# POW.net
KiCad netlist of a schematic drawn in Altium Designer
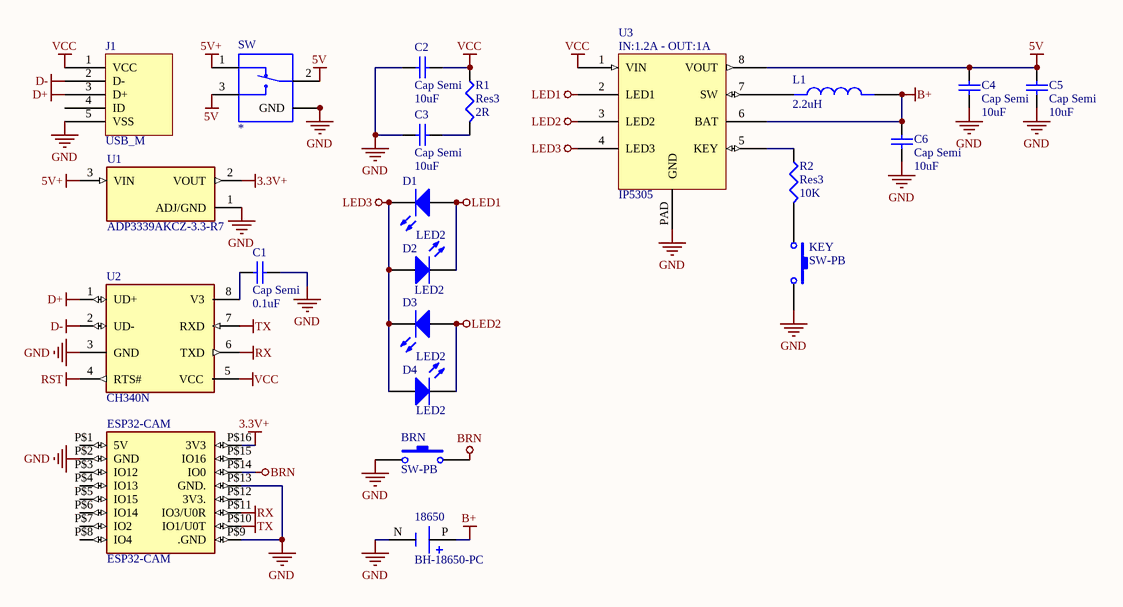
[diagram p0: POW.SchDoc]

(export (version "E")
  (design (tool "Eeschema 10.0.6"))
  (components
    (comp (ref "18650")
      (value "BH-18650-PC")
      (footprint "BAT_BH-18650-PC")
      (description "Battery Holder _Open_ 18650 1 Cell PC Pin")
      (fields (field (name "MF") "MPD _Memory"))
      (libsource (lib "BH-18650-PC") (part "BH-18650-PC"))
    )
    (comp (ref "BRN")
      (value "SW-PB")
      (footprint "SW_PB2_B1")
      (description "峚雄羲壽")
      (fields (field (name "PUBLISHER") "Altium Limited"))
      (libsource (lib "Fszhang") (part "SW-PB"))
    )
    (comp (ref "C1")
      (value "Cap Semi")
      (footprint "C1206")
      (description "Capacitor (Semiconductor SIM Model)")
      (fields (field (name "ALTIUM_VALUE") "0.1uF") (field (name "PUBLISHER") "Altium Limited"))
      (libsource (lib "Miscellaneous Devices") (part "Cap Semi"))
    )
    (comp (ref "C2")
      (value "Cap Semi")
      (footprint "C1210")
      (description "Capacitor (Semiconductor SIM Model)")
      (fields (field (name "ALTIUM_VALUE") "10uF") (field (name "PUBLISHER") "Altium Limited"))
      (libsource (lib "Miscellaneous Devices") (part "Cap Semi"))
    )
    (comp (ref "C3")
      (value "Cap Semi")
      (footprint "C1210")
      (description "Capacitor (Semiconductor SIM Model)")
      (fields (field (name "ALTIUM_VALUE") "10uF") (field (name "PUBLISHER") "Altium Limited"))
      (libsource (lib "Miscellaneous Devices") (part "Cap Semi"))
    )
    (comp (ref "C4")
      (value "Cap Semi")
      (footprint "C1210")
      (description "Capacitor (Semiconductor SIM Model)")
      (fields (field (name "ALTIUM_VALUE") "10uF") (field (name "PUBLISHER") "Altium Limited"))
      (libsource (lib "Miscellaneous Devices") (part "Cap Semi"))
    )
    (comp (ref "C5")
      (value "Cap Semi")
      (footprint "C1210")
      (description "Capacitor (Semiconductor SIM Model)")
      (fields (field (name "ALTIUM_VALUE") "10uF") (field (name "PUBLISHER") "Altium Limited"))
      (libsource (lib "Miscellaneous Devices") (part "Cap Semi"))
    )
    (comp (ref "C6")
      (value "Cap Semi")
      (footprint "C1210")
      (description "Capacitor (Semiconductor SIM Model)")
      (fields (field (name "ALTIUM_VALUE") "10uF") (field (name "PUBLISHER") "Altium Limited"))
      (libsource (lib "Miscellaneous Devices") (part "Cap Semi"))
    )
    (comp (ref "D1")
      (value "LED2")
      (footprint "3.2X1.6X1.1")
      (description "Typical RED, GREEN, YELLOW, AMBER GaAs LED")
      (fields (field (name "PUBLISHER") "Altium Limited"))
      (libsource (lib "Miscellaneous Devices") (part "LED2"))
    )
    (comp (ref "D2")
      (value "LED2")
      (footprint "3.2X1.6X1.1")
      (description "Typical RED, GREEN, YELLOW, AMBER GaAs LED")
      (fields (field (name "PUBLISHER") "Altium Limited"))
      (libsource (lib "Miscellaneous Devices") (part "LED2"))
    )
    (comp (ref "D3")
      (value "LED2")
      (footprint "3.2X1.6X1.1")
      (description "Typical RED, GREEN, YELLOW, AMBER GaAs LED")
      (fields (field (name "PUBLISHER") "Altium Limited"))
      (libsource (lib "Miscellaneous Devices") (part "LED2"))
    )
    (comp (ref "D4")
      (value "LED2")
      (footprint "3.2X1.6X1.1")
      (description "Typical RED, GREEN, YELLOW, AMBER GaAs LED")
      (fields (field (name "PUBLISHER") "Altium Limited"))
      (libsource (lib "Miscellaneous Devices") (part "LED2"))
    )
    (comp (ref "ESP32-CAM")
      (value "ESP32-CAM")
      (footprint "ESP32-CAM")
      (description "The smallest 802.11b/g/n Wi-Fi BT SoC Module")
      (fields (field (name "MF") "AI-Thinker"))
      (libsource (lib "ESP32-CAM") (part "ESP32-CAM"))
    )
    (comp (ref "J1")
      (value "USB_M")
      (footprint "USB_MICRO")
      (description "MicroUSB諉諳")
      (libsource (lib "Fszhang") (part "USB_M"))
    )
    (comp (ref "KEY")
      (value "SW-PB")
      (footprint "SW_PB2_B1")
      (description "峚雄羲壽")
      (fields (field (name "PUBLISHER") "Altium Limited"))
      (libsource (lib "Fszhang") (part "SW-PB"))
    )
    (comp (ref "L1")
      (value "2.2uH")
      (footprint "IND_1253AY-100M=P3")
      (description "Inductor with Inductance: 10uH Tol. +/-20%, Package: 2424 (6060)")
      (fields (field (name "MF") "Murata") (field (name "MP") "1253AY-100M=P3"))
      (libsource (lib "1253AY-100M_P3") (part "1253AY-100M=P3"))
    )
    (comp (ref "R1")
      (value "Res3")
      (footprint "J1-0603")
      (description "Resistor")
      (fields (field (name "ALTIUM_VALUE") "2R") (field (name "PUBLISHER") "Altium Limited"))
      (libsource (lib "Miscellaneous Devices") (part "Res3"))
    )
    (comp (ref "R2")
      (value "Res3")
      (footprint "J1-0603")
      (description "Resistor")
      (fields (field (name "ALTIUM_VALUE") "10K") (field (name "PUBLISHER") "Altium Limited"))
      (libsource (lib "Miscellaneous Devices") (part "Res3"))
    )
    (comp (ref "SW")
      (value "1437575-1")
      (footprint "SW_MLL1200S")
      (description "Slide Switch SPDT Surface Mount, Right Angle")
      (fields
        (field (name "MF") "TE Connectivity")
        (field (name "DIGI-KEY_PART_NUMBER") "450-1577-ND")
        (field (name "COMMENT_1") "*")
      )
      (libsource (lib "MLL1200S") (part "MLL1200S"))
    )
    (comp (ref "U1")
      (value "ADP3339AKCZ-3.3-R7")
      (footprint "SOT229P700X180-4N")
      (description "Sot223/Pkg 1-Amp 3.3-Volt Low Drop Out Voltage Regulatator")
      (fields (field (name "MP") "AMS1117-3.3") (field (name "MF") "Advanced Monolithic Systems"))
      (libsource (lib "AMS1117-3.3") (part "AMS1117-3.3"))
    )
    (comp (ref "U2")
      (value "CH340N")
      (footprint "SOP-8")
      (description "Complete single cell Li-Ion battery with a constant current / constant voltage linear charger")
      (fields (field (name "MP") "TP4056") (field (name "MF") "NanJing Top Power ASIC Corp."))
      (libsource (lib "CH340N") (part "CH340N"))
    )
    (comp (ref "U3") (value "IP5305") (footprint "SOP-8") (libsource (lib "IP530X") (part "IP5305")))
  )
  (nets
    (net (code "1") (name "3.3V+") (class "Default")
      (node (ref "ESP32-CAM") (pin "P$16") (pinfunction "3V3_P$16") (pintype "bidirectional"))
      (node (ref "U1") (pin "2") (pinfunction "VOUT_2") (pintype "output"))
    )
    (net (code "2") (name "5V") (class "Default")
      (node (ref "C4") (pin "2") (pinfunction "2_2") (pintype "passive"))
      (node (ref "C5") (pin "2") (pinfunction "2_2") (pintype "passive"))
      (node (ref "SW") (pin "2") (pinfunction "2_2") (pintype "passive"))
      (node (ref "SW") (pin "3") (pinfunction "3_3") (pintype "passive"))
      (node (ref "U3") (pin "8") (pinfunction "VOUT_8") (pintype "output"))
    )
    (net (code "3") (name "5V+") (class "Default")
      (node (ref "SW") (pin "1") (pinfunction "1_1") (pintype "passive"))
      (node (ref "U1") (pin "3") (pinfunction "VIN_3") (pintype "input"))
    )
    (net (code "4") (name "B+") (class "Default")
      (node (ref "18650") (pin "P") (pinfunction "POS_P") (pintype "passive"))
      (node (ref "C6") (pin "2") (pinfunction "2_2") (pintype "passive"))
      (node (ref "L1") (pin "2") (pinfunction "2_2") (pintype "passive"))
      (node (ref "U3") (pin "6") (pinfunction "BAT_6") (pintype "passive"))
    )
    (net (code "5") (name "BRN") (class "Default")
      (node (ref "BRN") (pin "2") (pinfunction "2_2") (pintype "passive"))
      (node (ref "ESP32-CAM") (pin "P$14") (pinfunction "IO0_P$14") (pintype "bidirectional"))
    )
    (net (code "6") (name "D+") (class "Default")
      (node (ref "J1") (pin "3") (pinfunction "D+_3") (pintype "passive"))
      (node (ref "U2") (pin "1") (pinfunction "UD+_1") (pintype "bidirectional"))
    )
    (net (code "7") (name "D-") (class "Default")
      (node (ref "J1") (pin "2") (pinfunction "D-_2") (pintype "passive"))
      (node (ref "U2") (pin "2") (pinfunction "UD-_2") (pintype "bidirectional"))
    )
    (net (code "8") (name "GND") (class "Default")
      (node (ref "18650") (pin "N") (pinfunction "NEG_N") (pintype "passive"))
      (node (ref "BRN") (pin "1") (pinfunction "1_1") (pintype "passive"))
      (node (ref "C1") (pin "2") (pinfunction "2_2") (pintype "passive"))
      (node (ref "C2") (pin "1") (pinfunction "1_1") (pintype "passive"))
      (node (ref "C3") (pin "2") (pinfunction "2_2") (pintype "passive"))
      (node (ref "C4") (pin "1") (pinfunction "1_1") (pintype "passive"))
      (node (ref "C5") (pin "1") (pinfunction "1_1") (pintype "passive"))
      (node (ref "C6") (pin "1") (pinfunction "1_1") (pintype "passive"))
      (node (ref "ESP32-CAM") (pin "P$13") (pinfunction "GND._P$13") (pintype "bidirectional"))
      (node (ref "ESP32-CAM") (pin "P$2") (pinfunction "GND_P$2") (pintype "bidirectional"))
      (node (ref "ESP32-CAM") (pin "P$9") (pinfunction ".GND_P$9") (pintype "bidirectional"))
      (node (ref "J1") (pin "5") (pinfunction "VSS_5") (pintype "passive"))
      (node (ref "KEY") (pin "2") (pinfunction "2_2") (pintype "passive"))
      (node (ref "SW") (pin "G1") (pinfunction "GND_G1") (pintype "power_in"))
      (node (ref "SW") (pin "G2") (pinfunction "GND_G2") (pintype "power_in"))
      (node (ref "SW") (pin "G3") (pinfunction "GND_G3") (pintype "power_in"))
      (node (ref "SW") (pin "G4") (pinfunction "GND_G4") (pintype "power_in"))
      (node (ref "U1") (pin "1") (pinfunction "ADJ/GND_1") (pintype "power_in"))
      (node (ref "U2") (pin "3") (pinfunction "GND_3") (pintype "open_collector"))
      (node (ref "U3") (pin "PAD") (pinfunction "GND_PAD") (pintype "passive"))
    )
    (net (code "9") (name "LED1") (class "Default")
      (node (ref "D1") (pin "1") (pinfunction "A_1") (pintype "passive"))
      (node (ref "D2") (pin "2") (pinfunction "K_2") (pintype "passive"))
      (node (ref "U3") (pin "2") (pinfunction "LED1_2") (pintype "passive"))
    )
    (net (code "10") (name "LED2") (class "Default")
      (node (ref "D3") (pin "1") (pinfunction "A_1") (pintype "passive"))
      (node (ref "D4") (pin "2") (pinfunction "K_2") (pintype "passive"))
      (node (ref "U3") (pin "3") (pinfunction "LED2_3") (pintype "passive"))
    )
    (net (code "11") (name "LED3") (class "Default")
      (node (ref "D1") (pin "2") (pinfunction "K_2") (pintype "passive"))
      (node (ref "D2") (pin "1") (pinfunction "A_1") (pintype "passive"))
      (node (ref "D3") (pin "2") (pinfunction "K_2") (pintype "passive"))
      (node (ref "D4") (pin "1") (pinfunction "A_1") (pintype "passive"))
      (node (ref "U3") (pin "4") (pinfunction "LED3_4") (pintype "passive"))
    )
    (net (code "12") (name "Net-(C3-Pad1)") (class "Default")
      (node (ref "C3") (pin "1") (pinfunction "1_1") (pintype "passive"))
      (node (ref "R1") (pin "2") (pinfunction "2_2") (pintype "passive"))
    )
    (net (code "13") (name "Net-(KEY-Pad1)") (class "Default")
      (node (ref "KEY") (pin "1") (pinfunction "1_1") (pintype "passive"))
      (node (ref "R2") (pin "2") (pinfunction "2_2") (pintype "passive"))
    )
    (net (code "14") (name "Net-(U2-V3)") (class "Default")
      (node (ref "C1") (pin "1") (pinfunction "1_1") (pintype "passive"))
      (node (ref "U2") (pin "8") (pinfunction "V3_8") (pintype "open_collector"))
    )
    (net (code "15") (name "Net-(U3-KEY)") (class "Default")
      (node (ref "R2") (pin "1") (pinfunction "1_1") (pintype "passive"))
      (node (ref "U3") (pin "5") (pinfunction "KEY_5") (pintype "bidirectional"))
    )
    (net (code "16") (name "Net-(U3-SW)") (class "Default")
      (node (ref "L1") (pin "1") (pinfunction "1_1") (pintype "passive"))
      (node (ref "U3") (pin "7") (pinfunction "SW_7") (pintype "bidirectional"))
    )
    (net (code "17") (name "RST") (class "Default")
      (node (ref "U2") (pin "4") (pinfunction "RTS#_4") (pintype "output"))
    )
    (net (code "18") (name "RX") (class "Default")
      (node (ref "ESP32-CAM") (pin "P$11") (pinfunction "IO3/U0R_P$11") (pintype "bidirectional"))
      (node (ref "U2") (pin "6") (pinfunction "TXD_6") (pintype "output"))
    )
    (net (code "19") (name "TX") (class "Default")
      (node (ref "ESP32-CAM") (pin "P$10") (pinfunction "IO1/U0T_P$10") (pintype "bidirectional"))
      (node (ref "U2") (pin "7") (pinfunction "RXD_7") (pintype "input"))
    )
    (net (code "20") (name "VCC") (class "Default")
      (node (ref "C2") (pin "2") (pinfunction "2_2") (pintype "passive"))
      (node (ref "J1") (pin "1") (pinfunction "VCC_1") (pintype "passive"))
      (node (ref "R1") (pin "1") (pinfunction "1_1") (pintype "passive"))
      (node (ref "U2") (pin "5") (pinfunction "VCC_5") (pintype "open_collector"))
      (node (ref "U3") (pin "1") (pinfunction "VIN_1") (pintype "input"))
    )
    (net (code "21") (name "unconnected-(ESP32-CAM-3V3.-PadP$12)") (class "Default")
      (node (ref "ESP32-CAM") (pin "P$12") (pinfunction "3V3._P$12") (pintype "bidirectional"))
    )
    (net (code "22") (name "unconnected-(ESP32-CAM-5V-PadP$1)") (class "Default")
      (node (ref "ESP32-CAM") (pin "P$1") (pinfunction "5V_P$1") (pintype "bidirectional"))
    )
    (net (code "23") (name "unconnected-(ESP32-CAM-IO2-PadP$7)") (class "Default")
      (node (ref "ESP32-CAM") (pin "P$7") (pinfunction "IO2_P$7") (pintype "bidirectional"))
    )
    (net (code "24") (name "unconnected-(ESP32-CAM-IO4-PadP$8)") (class "Default")
      (node (ref "ESP32-CAM") (pin "P$8") (pinfunction "IO4_P$8") (pintype "bidirectional"))
    )
    (net (code "25") (name "unconnected-(ESP32-CAM-IO12-PadP$3)") (class "Default")
      (node (ref "ESP32-CAM") (pin "P$3") (pinfunction "IO12_P$3") (pintype "bidirectional"))
    )
    (net (code "26") (name "unconnected-(ESP32-CAM-IO13-PadP$4)") (class "Default")
      (node (ref "ESP32-CAM") (pin "P$4") (pinfunction "IO13_P$4") (pintype "bidirectional"))
    )
    (net (code "27") (name "unconnected-(ESP32-CAM-IO14-PadP$6)") (class "Default")
      (node (ref "ESP32-CAM") (pin "P$6") (pinfunction "IO14_P$6") (pintype "bidirectional"))
    )
    (net (code "28") (name "unconnected-(ESP32-CAM-IO15-PadP$5)") (class "Default")
      (node (ref "ESP32-CAM") (pin "P$5") (pinfunction "IO15_P$5") (pintype "bidirectional"))
    )
    (net (code "29") (name "unconnected-(ESP32-CAM-IO16-PadP$15)") (class "Default")
      (node (ref "ESP32-CAM") (pin "P$15") (pinfunction "IO16_P$15") (pintype "bidirectional"))
    )
    (net (code "30") (name "unconnected-(J1-ID-Pad4)") (class "Default")
      (node (ref "J1") (pin "4") (pinfunction "ID_4") (pintype "passive"))
    )
  )
)
